# i2c_proximity.net
KiCad netlist of a schematic drawn in EAGLE
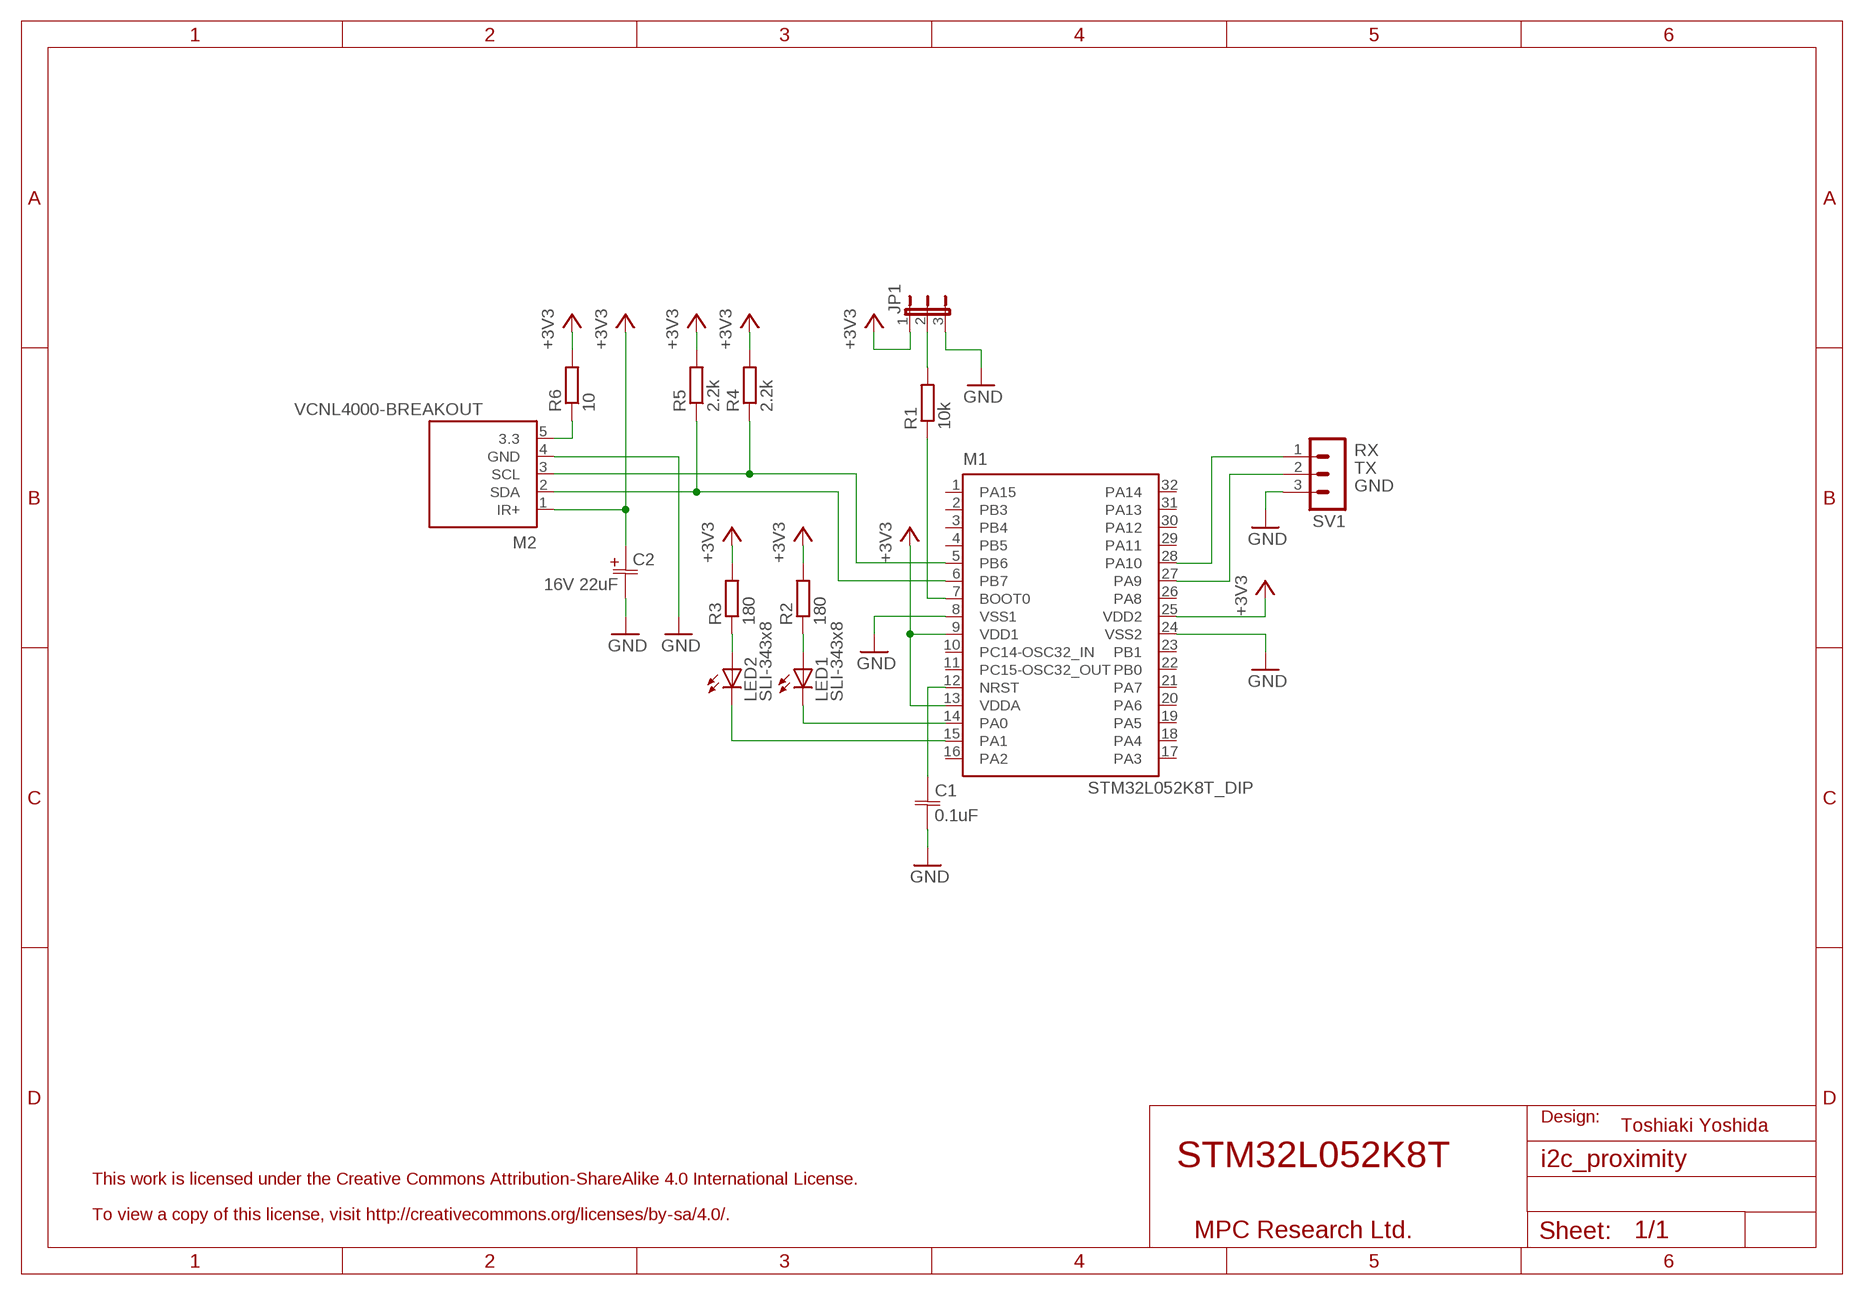
[diagram p0: schematic, sheet 1]

(export (version "E")
  (design (tool "Eeschema 10.0.6"))
  (components
    (comp (ref "C1")
      (value "0.1uF")
      (footprint "eagle-import:C050-024X044")
      (libsource (lib "eagle-import") (part "C-JIS050-024X044"))
    )
    (comp (ref "C2")
      (value "16V 22uF")
      (footprint "eagle-import:E2,5-5")
      (libsource (lib "eagle-import") (part "CPOL-JIS"))
    )
    (comp (ref "JP1")
      (value "JP2E")
      (footprint "eagle-import:JP2")
      (libsource (lib "eagle-import") (part "JP2E"))
    )
    (comp (ref "LED1")
      (value "SLI-343x8")
      (footprint "eagle-import:LED3MM")
      (libsource (lib "eagle-import") (part "LED3MM"))
    )
    (comp (ref "LED2")
      (value "SLI-343x8")
      (footprint "eagle-import:LED3MM")
      (libsource (lib "eagle-import") (part "LED3MM"))
    )
    (comp (ref "M1")
      (value "STM32L052K8T_DIP")
      (footprint "eagle-import:DIP32")
      (libsource (lib "eagle-import") (part "STM32L052K8T_DIP"))
    )
    (comp (ref "M2")
      (value "VCNL4000-BREAKOUT")
      (footprint "eagle-import:VCNL4000-BREAKOUT")
      (libsource (lib "eagle-import") (part "VCNL4000-BREAKOUT"))
    )
    (comp (ref "R1")
      (value "10k")
      (footprint "eagle-import:0207_2V")
      (libsource (lib "eagle-import") (part "R-EU_0207/2V"))
    )
    (comp (ref "R2")
      (value "180")
      (footprint "eagle-import:0207_2V")
      (libsource (lib "eagle-import") (part "R-EU_0207/2V"))
    )
    (comp (ref "R3")
      (value "180")
      (footprint "eagle-import:0207_2V")
      (libsource (lib "eagle-import") (part "R-EU_0207/2V"))
    )
    (comp (ref "R4")
      (value "2.2k")
      (footprint "eagle-import:0207_2V")
      (libsource (lib "eagle-import") (part "R-EU_0207/2V"))
    )
    (comp (ref "R5")
      (value "2.2k")
      (footprint "eagle-import:0207_2V")
      (libsource (lib "eagle-import") (part "R-EU_0207/2V"))
    )
    (comp (ref "R6")
      (value "10")
      (footprint "eagle-import:0207_2V")
      (libsource (lib "eagle-import") (part "R-EU_0207/2V"))
    )
    (comp (ref "SV1")
      (value "MA03-1")
      (footprint "eagle-import:MA03-1")
      (libsource (lib "eagle-import") (part "MA03-1"))
    )
  )
  (nets
    (net (code "1") (name "+3V3") (class "Default")
      (node (ref "C2") (pin "+") (pinfunction "+_+") (pintype "passive"))
      (node (ref "JP1") (pin "1") (pinfunction "1_1") (pintype "passive"))
      (node (ref "M1") (pin "13") (pinfunction "VDDA_13") (pintype "power_in"))
      (node (ref "M1") (pin "25") (pinfunction "VDD2_25") (pintype "bidirectional"))
      (node (ref "M1") (pin "9") (pinfunction "VDD1_9") (pintype "power_in"))
      (node (ref "M2") (pin "1") (pinfunction "IR+_1") (pintype "power_in"))
      (node (ref "R2") (pin "2") (pinfunction "2_2") (pintype "passive"))
      (node (ref "R3") (pin "2") (pinfunction "2_2") (pintype "passive"))
      (node (ref "R4") (pin "2") (pinfunction "2_2") (pintype "passive"))
      (node (ref "R5") (pin "2") (pinfunction "2_2") (pintype "passive"))
      (node (ref "R6") (pin "2") (pinfunction "2_2") (pintype "passive"))
    )
    (net (code "2") (name "GND") (class "Default")
      (node (ref "C1") (pin "2") (pinfunction "2_2") (pintype "passive"))
      (node (ref "C2") (pin "-") (pinfunction "-_-") (pintype "passive"))
      (node (ref "JP1") (pin "3") (pinfunction "3_3") (pintype "passive"))
      (node (ref "M1") (pin "24") (pinfunction "VSS2_24") (pintype "power_in"))
      (node (ref "M1") (pin "8") (pinfunction "VSS1_8") (pintype "power_in"))
      (node (ref "M2") (pin "4") (pinfunction "GND_4") (pintype "power_in"))
      (node (ref "SV1") (pin "3") (pinfunction "3_3") (pintype "passive"))
    )
    (net (code "3") (name "Net-(JP1-Pad2)") (class "Default")
      (node (ref "JP1") (pin "2") (pinfunction "2_2") (pintype "passive"))
      (node (ref "R1") (pin "2") (pinfunction "2_2") (pintype "passive"))
    )
    (net (code "4") (name "Net-(LED1-C)") (class "Default")
      (node (ref "LED1") (pin "K") (pinfunction "C_K") (pintype "passive"))
      (node (ref "M1") (pin "14") (pinfunction "PA0_14") (pintype "bidirectional"))
    )
    (net (code "5") (name "Net-(LED1-PadA)") (class "Default")
      (node (ref "LED1") (pin "A") (pinfunction "A_A") (pintype "passive"))
      (node (ref "R2") (pin "1") (pinfunction "1_1") (pintype "passive"))
    )
    (net (code "6") (name "Net-(LED2-C)") (class "Default")
      (node (ref "LED2") (pin "K") (pinfunction "C_K") (pintype "passive"))
      (node (ref "M1") (pin "15") (pinfunction "PA1_15") (pintype "bidirectional"))
    )
    (net (code "7") (name "Net-(LED2-PadA)") (class "Default")
      (node (ref "LED2") (pin "A") (pinfunction "A_A") (pintype "passive"))
      (node (ref "R3") (pin "1") (pinfunction "1_1") (pintype "passive"))
    )
    (net (code "8") (name "Net-(M1-BOOT0)") (class "Default")
      (node (ref "M1") (pin "7") (pinfunction "BOOT0_7") (pintype "bidirectional"))
      (node (ref "R1") (pin "1") (pinfunction "1_1") (pintype "passive"))
    )
    (net (code "9") (name "Net-(M1-NRST)") (class "Default")
      (node (ref "C1") (pin "1") (pinfunction "1_1") (pintype "passive"))
      (node (ref "M1") (pin "12") (pinfunction "NRST_12") (pintype "bidirectional"))
    )
    (net (code "10") (name "Net-(M1-PA9)") (class "Default")
      (node (ref "M1") (pin "27") (pinfunction "PA9_27") (pintype "bidirectional"))
      (node (ref "SV1") (pin "2") (pinfunction "2_2") (pintype "passive"))
    )
    (net (code "11") (name "Net-(M1-PA10)") (class "Default")
      (node (ref "M1") (pin "28") (pinfunction "PA10_28") (pintype "bidirectional"))
      (node (ref "SV1") (pin "1") (pinfunction "1_1") (pintype "passive"))
    )
    (net (code "12") (name "Net-(M1-PB6)") (class "Default")
      (node (ref "M1") (pin "5") (pinfunction "PB6_5") (pintype "bidirectional"))
      (node (ref "M2") (pin "3") (pinfunction "SCL_3") (pintype "input"))
      (node (ref "R4") (pin "1") (pinfunction "1_1") (pintype "passive"))
    )
    (net (code "13") (name "Net-(M1-PB7)") (class "Default")
      (node (ref "M1") (pin "6") (pinfunction "PB7_6") (pintype "bidirectional"))
      (node (ref "M2") (pin "2") (pinfunction "SDA_2") (pintype "open_collector"))
      (node (ref "R5") (pin "1") (pinfunction "1_1") (pintype "passive"))
    )
    (net (code "14") (name "Net-(M2-3.3)") (class "Default")
      (node (ref "M2") (pin "5") (pinfunction "3.3_5") (pintype "power_in"))
      (node (ref "R6") (pin "1") (pinfunction "1_1") (pintype "passive"))
    )
    (net (code "15") (name "unconnected-(M1-PA2-Pad16)") (class "Default")
      (node (ref "M1") (pin "16") (pinfunction "PA2_16") (pintype "bidirectional"))
    )
    (net (code "16") (name "unconnected-(M1-PA3-Pad17)") (class "Default")
      (node (ref "M1") (pin "17") (pinfunction "PA3_17") (pintype "bidirectional"))
    )
    (net (code "17") (name "unconnected-(M1-PA4-Pad18)") (class "Default")
      (node (ref "M1") (pin "18") (pinfunction "PA4_18") (pintype "bidirectional"))
    )
    (net (code "18") (name "unconnected-(M1-PA5-Pad19)") (class "Default")
      (node (ref "M1") (pin "19") (pinfunction "PA5_19") (pintype "bidirectional"))
    )
    (net (code "19") (name "unconnected-(M1-PA6-Pad20)") (class "Default")
      (node (ref "M1") (pin "20") (pinfunction "PA6_20") (pintype "bidirectional"))
    )
    (net (code "20") (name "unconnected-(M1-PA7-Pad21)") (class "Default")
      (node (ref "M1") (pin "21") (pinfunction "PA7_21") (pintype "bidirectional"))
    )
    (net (code "21") (name "unconnected-(M1-PA8-Pad26)") (class "Default")
      (node (ref "M1") (pin "26") (pinfunction "PA8_26") (pintype "bidirectional"))
    )
    (net (code "22") (name "unconnected-(M1-PA11-Pad29)") (class "Default")
      (node (ref "M1") (pin "29") (pinfunction "PA11_29") (pintype "bidirectional"))
    )
    (net (code "23") (name "unconnected-(M1-PA12-Pad30)") (class "Default")
      (node (ref "M1") (pin "30") (pinfunction "PA12_30") (pintype "bidirectional"))
    )
    (net (code "24") (name "unconnected-(M1-PA13-Pad31)") (class "Default")
      (node (ref "M1") (pin "31") (pinfunction "PA13_31") (pintype "bidirectional"))
    )
    (net (code "25") (name "unconnected-(M1-PA14-Pad32)") (class "Default")
      (node (ref "M1") (pin "32") (pinfunction "PA14_32") (pintype "bidirectional"))
    )
    (net (code "26") (name "unconnected-(M1-PA15-Pad1)") (class "Default")
      (node (ref "M1") (pin "1") (pinfunction "PA15_1") (pintype "bidirectional"))
    )
    (net (code "27") (name "unconnected-(M1-PB0-Pad22)") (class "Default")
      (node (ref "M1") (pin "22") (pinfunction "PB0_22") (pintype "bidirectional"))
    )
    (net (code "28") (name "unconnected-(M1-PB1-Pad23)") (class "Default")
      (node (ref "M1") (pin "23") (pinfunction "PB1_23") (pintype "bidirectional"))
    )
    (net (code "29") (name "unconnected-(M1-PB3-Pad2)") (class "Default")
      (node (ref "M1") (pin "2") (pinfunction "PB3_2") (pintype "bidirectional"))
    )
    (net (code "30") (name "unconnected-(M1-PB4-Pad3)") (class "Default")
      (node (ref "M1") (pin "3") (pinfunction "PB4_3") (pintype "bidirectional"))
    )
    (net (code "31") (name "unconnected-(M1-PB5-Pad4)") (class "Default")
      (node (ref "M1") (pin "4") (pinfunction "PB5_4") (pintype "bidirectional"))
    )
    (net (code "32") (name "unconnected-(M1-PC14-OSC32_IN-Pad10)") (class "Default")
      (node (ref "M1") (pin "10") (pinfunction "PC14-OSC32_IN_10") (pintype "bidirectional"))
    )
    (net (code "33") (name "unconnected-(M1-PC15-OSC32_OUT-Pad11)") (class "Default")
      (node (ref "M1") (pin "11") (pinfunction "PC15-OSC32_OUT_11") (pintype "bidirectional"))
    )
  )
)
